# modem_tda.net
KiCad netlist of a schematic drawn in EAGLE
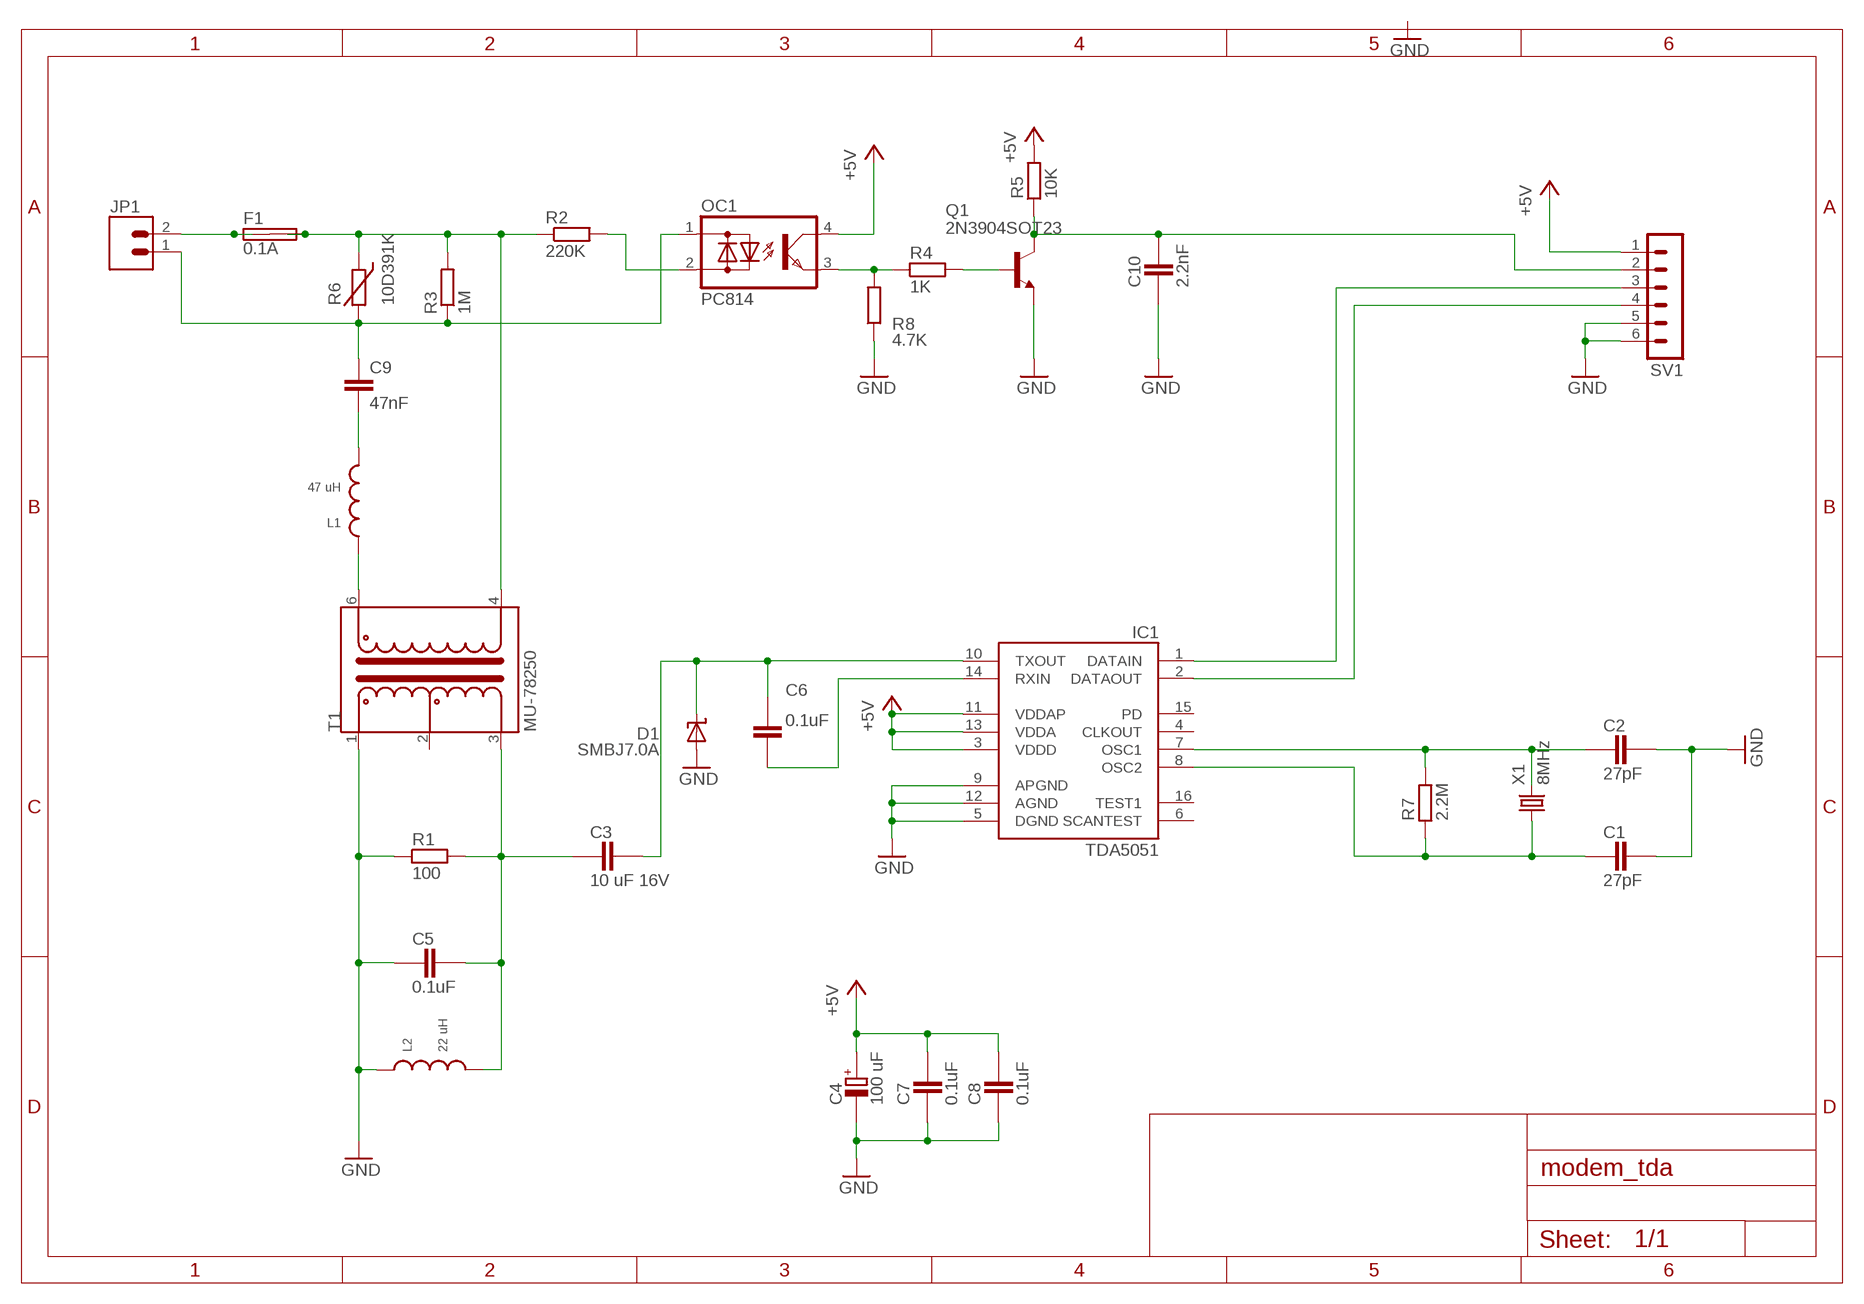
[diagram p0: schematic, sheet 1]

(export (version "E")
  (design (tool "Eeschema 10.0.6"))
  (components
    (comp (ref "C1")
      (value "27pF")
      (footprint "eagle-import:CAPC2012X145AN")
      (libsource (lib "eagle-import") (part "CAPACITOR_0805"))
    )
    (comp (ref "C2")
      (value "27pF")
      (footprint "eagle-import:CAPC2012X145AN")
      (libsource (lib "eagle-import") (part "CAPACITOR_0805"))
    )
    (comp (ref "C3")
      (value "10 uF 16V")
      (footprint "eagle-import:CAPC3215X168N")
      (libsource (lib "eagle-import") (part "CAPACITOR_1206"))
    )
    (comp (ref "C4")
      (value "100 uF")
      (footprint "eagle-import:CAPMP6032X150N")
      (libsource (lib "eagle-import") (part "POLARISED_U_CASE"))
    )
    (comp (ref "C5")
      (value "0.1uF")
      (footprint "eagle-import:CAPC2012X145AN")
      (libsource (lib "eagle-import") (part "CAPACITOR_0805"))
    )
    (comp (ref "C6")
      (value "0.1uF")
      (footprint "eagle-import:CAPC2012X145AN")
      (libsource (lib "eagle-import") (part "CAPACITOR_0805"))
    )
    (comp (ref "C7")
      (value "0.1uF")
      (footprint "eagle-import:CAPC2012X145AN")
      (libsource (lib "eagle-import") (part "CAPACITOR_0805"))
    )
    (comp (ref "C8")
      (value "0.1uF")
      (footprint "eagle-import:CAPC2012X145AN")
      (libsource (lib "eagle-import") (part "CAPACITOR_0805"))
    )
    (comp (ref "C9")
      (value "47nF")
      (footprint "eagle-import:XC10B6")
      (libsource (lib "eagle-import") (part "CXXC10B6"))
    )
    (comp (ref "C10")
      (value "2.2nF")
      (footprint "eagle-import:CAPC2012X145AN")
      (libsource (lib "eagle-import") (part "CAPACITOR_0805"))
    )
    (comp (ref "D1")
      (value "SMBJ7.0A")
      (footprint "eagle-import:SMBJ")
      (libsource (lib "eagle-import") (part "SUPPRESSOR-SMBJ"))
    )
    (comp (ref "F1")
      (value "0.1A")
      (footprint "eagle-import:SHK20L")
      (libsource (lib "eagle-import") (part "SHK20L"))
    )
    (comp (ref "IC1")
      (value "TDA5051")
      (footprint "eagle-import:SO16W")
      (libsource (lib "eagle-import") (part "TDA5051"))
    )
    (comp (ref "JP1")
      (value "BLUE_TERM")
      (footprint "eagle-import:BLUE_TERM")
      (libsource (lib "eagle-import") (part "BLUE_TERM"))
    )
    (comp (ref "L1")
      (value "47 uH")
      (footprint "eagle-import:CD43")
      (libsource (lib "eagle-import") (part "L-US"))
    )
    (comp (ref "L2")
      (value "22 uH")
      (footprint "eagle-import:CD43")
      (libsource (lib "eagle-import") (part "L-US"))
    )
    (comp (ref "OC1")
      (value "PC814")
      (footprint "eagle-import:DIL04")
      (libsource (lib "eagle-import") (part "PC814"))
    )
    (comp (ref "Q1")
      (value "2N3904SOT23")
      (footprint "eagle-import:SOT23-BEC")
      (libsource (lib "eagle-import") (part "2N3904SOT23"))
    )
    (comp (ref "R1")
      (value "100")
      (footprint "eagle-import:RESC2012X70N")
      (libsource (lib "eagle-import") (part "RESISTOR_0805"))
    )
    (comp (ref "R2")
      (value "220K")
      (footprint "eagle-import:0309_12")
      (libsource (lib "eagle-import") (part "R-EU_0309/12"))
    )
    (comp (ref "R3")
      (value "1M")
      (footprint "eagle-import:0207_10")
      (libsource (lib "eagle-import") (part "R-EU_0207/10"))
    )
    (comp (ref "R4")
      (value "1K")
      (footprint "eagle-import:RESC2012X70N")
      (libsource (lib "eagle-import") (part "RESISTOR_0805"))
    )
    (comp (ref "R5")
      (value "10K")
      (footprint "eagle-import:RESC2012X70N")
      (libsource (lib "eagle-import") (part "RESISTOR_0805"))
    )
    (comp (ref "R6")
      (value "10D391K")
      (footprint "eagle-import:MOV-10D")
      (libsource (lib "eagle-import") (part "VARISTOR"))
    )
    (comp (ref "R7")
      (value "2.2M")
      (footprint "eagle-import:RESC2012X70N")
      (libsource (lib "eagle-import") (part "RESISTOR_0805"))
    )
    (comp (ref "R8")
      (value "4.7K")
      (footprint "eagle-import:RESC2012X70N")
      (libsource (lib "eagle-import") (part "RESISTOR_0805"))
    )
    (comp (ref "SV1")
      (value "MA06-1")
      (footprint "eagle-import:MA06-1")
      (libsource (lib "eagle-import") (part "MA06-1"))
    )
    (comp (ref "T1")
      (value "MU-78250")
      (footprint "eagle-import:6-PIN-DIL")
      (libsource (lib "eagle-import") (part "MU-78250"))
    )
    (comp (ref "X1")
      (value "8MHz")
      (footprint "eagle-import:HC49_S")
      (libsource (lib "eagle-import") (part "CRYSTALHC49S"))
    )
  )
  (nets
    (net (code "1") (name "+5V") (class "Default")
      (node (ref "C4") (pin "+") (pinfunction "+_+") (pintype "passive"))
      (node (ref "C7") (pin "2") (pinfunction "2_2") (pintype "passive"))
      (node (ref "C8") (pin "2") (pinfunction "2_2") (pintype "passive"))
      (node (ref "IC1") (pin "11") (pinfunction "VDDAP_11") (pintype "power_in"))
      (node (ref "IC1") (pin "13") (pinfunction "VDDA_13") (pintype "power_in"))
      (node (ref "IC1") (pin "3") (pinfunction "VDDD_3") (pintype "power_in"))
      (node (ref "OC1") (pin "4") (pinfunction "C_4") (pintype "passive"))
      (node (ref "R5") (pin "2") (pinfunction "2_2") (pintype "passive"))
      (node (ref "SV1") (pin "1") (pinfunction "1_1") (pintype "passive"))
    )
    (net (code "2") (name "GND") (class "Default")
      (node (ref "C1") (pin "2") (pinfunction "2_2") (pintype "passive"))
      (node (ref "C10") (pin "1") (pinfunction "1_1") (pintype "passive"))
      (node (ref "C2") (pin "2") (pinfunction "2_2") (pintype "passive"))
      (node (ref "C4") (pin "-") (pinfunction "-_-") (pintype "passive"))
      (node (ref "C5") (pin "1") (pinfunction "1_1") (pintype "passive"))
      (node (ref "C7") (pin "1") (pinfunction "1_1") (pintype "passive"))
      (node (ref "C8") (pin "1") (pinfunction "1_1") (pintype "passive"))
      (node (ref "D1") (pin "A") (pinfunction "A_A") (pintype "passive"))
      (node (ref "IC1") (pin "12") (pinfunction "AGND_12") (pintype "power_in"))
      (node (ref "IC1") (pin "5") (pinfunction "DGND_5") (pintype "power_in"))
      (node (ref "IC1") (pin "9") (pinfunction "APGND_9") (pintype "bidirectional"))
      (node (ref "L2") (pin "1") (pinfunction "1_1") (pintype "bidirectional"))
      (node (ref "Q1") (pin "E") (pinfunction "E_E") (pintype "passive"))
      (node (ref "R1") (pin "1") (pinfunction "1_1") (pintype "passive"))
      (node (ref "R8") (pin "1") (pinfunction "1_1") (pintype "passive"))
      (node (ref "SV1") (pin "5") (pinfunction "5_5") (pintype "passive"))
      (node (ref "SV1") (pin "6") (pinfunction "6_6") (pintype "passive"))
      (node (ref "T1") (pin "1") (pinfunction "1_1") (pintype "bidirectional"))
    )
    (net (code "3") (name "Net-(C3-Pad1)") (class "Default")
      (node (ref "C3") (pin "1") (pinfunction "1_1") (pintype "passive"))
      (node (ref "C5") (pin "2") (pinfunction "2_2") (pintype "passive"))
      (node (ref "L2") (pin "2") (pinfunction "2_2") (pintype "bidirectional"))
      (node (ref "R1") (pin "2") (pinfunction "2_2") (pintype "passive"))
      (node (ref "T1") (pin "3") (pinfunction "3_3") (pintype "bidirectional"))
    )
    (net (code "4") (name "Net-(C9-Pad2)") (class "Default")
      (node (ref "C9") (pin "2") (pinfunction "2_2") (pintype "passive"))
      (node (ref "L1") (pin "2") (pinfunction "2_2") (pintype "bidirectional"))
    )
    (net (code "5") (name "Net-(C10-Pad2)") (class "Default")
      (node (ref "C10") (pin "2") (pinfunction "2_2") (pintype "passive"))
      (node (ref "Q1") (pin "C") (pinfunction "C_C") (pintype "passive"))
      (node (ref "R5") (pin "1") (pinfunction "1_1") (pintype "passive"))
      (node (ref "SV1") (pin "2") (pinfunction "2_2") (pintype "passive"))
    )
    (net (code "6") (name "Net-(F1-Pad1A)") (class "Default")
      (node (ref "F1") (pin "1A") (pinfunction "1A_1A") (pintype "passive"))
      (node (ref "F1") (pin "1B") (pinfunction "1B_1B") (pintype "passive"))
      (node (ref "JP1") (pin "2") (pinfunction "2_2") (pintype "passive"))
    )
    (net (code "7") (name "Net-(F1-Pad2A)") (class "Default")
      (node (ref "F1") (pin "2A") (pinfunction "2A_2A") (pintype "passive"))
      (node (ref "F1") (pin "2B") (pinfunction "2B_2B") (pintype "passive"))
      (node (ref "R2") (pin "1") (pinfunction "1_1") (pintype "passive"))
      (node (ref "R3") (pin "2") (pinfunction "2_2") (pintype "passive"))
      (node (ref "R6") (pin "2") (pinfunction "2_2") (pintype "bidirectional"))
      (node (ref "T1") (pin "4") (pinfunction "4_4") (pintype "bidirectional"))
    )
    (net (code "8") (name "Net-(IC1-DATAIN)") (class "Default")
      (node (ref "IC1") (pin "1") (pinfunction "DATAIN_1") (pintype "input"))
      (node (ref "SV1") (pin "3") (pinfunction "3_3") (pintype "passive"))
    )
    (net (code "9") (name "Net-(IC1-DATAOUT)") (class "Default")
      (node (ref "IC1") (pin "2") (pinfunction "DATAOUT_2") (pintype "output"))
      (node (ref "SV1") (pin "4") (pinfunction "4_4") (pintype "passive"))
    )
    (net (code "10") (name "Net-(IC1-OSC1)") (class "Default")
      (node (ref "C2") (pin "1") (pinfunction "1_1") (pintype "passive"))
      (node (ref "IC1") (pin "7") (pinfunction "OSC1_7") (pintype "bidirectional"))
      (node (ref "R7") (pin "2") (pinfunction "2_2") (pintype "passive"))
      (node (ref "X1") (pin "2") (pinfunction "2_2") (pintype "passive"))
    )
    (net (code "11") (name "Net-(IC1-OSC2)") (class "Default")
      (node (ref "C1") (pin "1") (pinfunction "1_1") (pintype "passive"))
      (node (ref "IC1") (pin "8") (pinfunction "OSC2_8") (pintype "bidirectional"))
      (node (ref "R7") (pin "1") (pinfunction "1_1") (pintype "passive"))
      (node (ref "X1") (pin "1") (pinfunction "1_1") (pintype "passive"))
    )
    (net (code "12") (name "Net-(IC1-RXIN)") (class "Default")
      (node (ref "C6") (pin "1") (pinfunction "1_1") (pintype "passive"))
      (node (ref "IC1") (pin "14") (pinfunction "RXIN_14") (pintype "input"))
    )
    (net (code "13") (name "Net-(IC1-TXOUT)") (class "Default")
      (node (ref "C3") (pin "2") (pinfunction "2_2") (pintype "passive"))
      (node (ref "C6") (pin "2") (pinfunction "2_2") (pintype "passive"))
      (node (ref "D1") (pin "C") (pinfunction "C_C") (pintype "passive"))
      (node (ref "IC1") (pin "10") (pinfunction "TXOUT_10") (pintype "output"))
    )
    (net (code "14") (name "Net-(L1-Pad1)") (class "Default")
      (node (ref "L1") (pin "1") (pinfunction "1_1") (pintype "bidirectional"))
      (node (ref "T1") (pin "6") (pinfunction "6_6") (pintype "bidirectional"))
    )
    (net (code "15") (name "Net-(OC1-AC1)") (class "Default")
      (node (ref "C9") (pin "1") (pinfunction "1_1") (pintype "passive"))
      (node (ref "JP1") (pin "1") (pinfunction "1_1") (pintype "passive"))
      (node (ref "OC1") (pin "1") (pinfunction "AC1_1") (pintype "passive"))
      (node (ref "R3") (pin "1") (pinfunction "1_1") (pintype "passive"))
      (node (ref "R6") (pin "1") (pinfunction "1_1") (pintype "bidirectional"))
    )
    (net (code "16") (name "Net-(OC1-AC2)") (class "Default")
      (node (ref "OC1") (pin "2") (pinfunction "AC2_2") (pintype "passive"))
      (node (ref "R2") (pin "2") (pinfunction "2_2") (pintype "passive"))
    )
    (net (code "17") (name "Net-(OC1-E)") (class "Default")
      (node (ref "OC1") (pin "3") (pinfunction "E_3") (pintype "passive"))
      (node (ref "R4") (pin "1") (pinfunction "1_1") (pintype "passive"))
      (node (ref "R8") (pin "2") (pinfunction "2_2") (pintype "passive"))
    )
    (net (code "18") (name "Net-(Q1-PadB)") (class "Default")
      (node (ref "Q1") (pin "B") (pinfunction "B_B") (pintype "passive"))
      (node (ref "R4") (pin "2") (pinfunction "2_2") (pintype "passive"))
    )
    (net (code "19") (name "unconnected-(IC1-CLKOUT-Pad4)") (class "Default")
      (node (ref "IC1") (pin "4") (pinfunction "CLKOUT_4") (pintype "output"))
    )
    (net (code "20") (name "unconnected-(IC1-PD-Pad15)") (class "Default")
      (node (ref "IC1") (pin "15") (pinfunction "PD_15") (pintype "input"))
    )
    (net (code "21") (name "unconnected-(IC1-SCANTEST-Pad6)") (class "Default")
      (node (ref "IC1") (pin "6") (pinfunction "SCANTEST_6") (pintype "bidirectional"))
    )
    (net (code "22") (name "unconnected-(IC1-TEST1-Pad16)") (class "Default")
      (node (ref "IC1") (pin "16") (pinfunction "TEST1_16") (pintype "bidirectional"))
    )
    (net (code "23") (name "unconnected-(T1-Pad2)") (class "Default")
      (node (ref "T1") (pin "2") (pinfunction "2_2") (pintype "bidirectional"))
    )
  )
)
